# pulseoxintegr.net
KiCad netlist of a schematic drawn in EAGLE
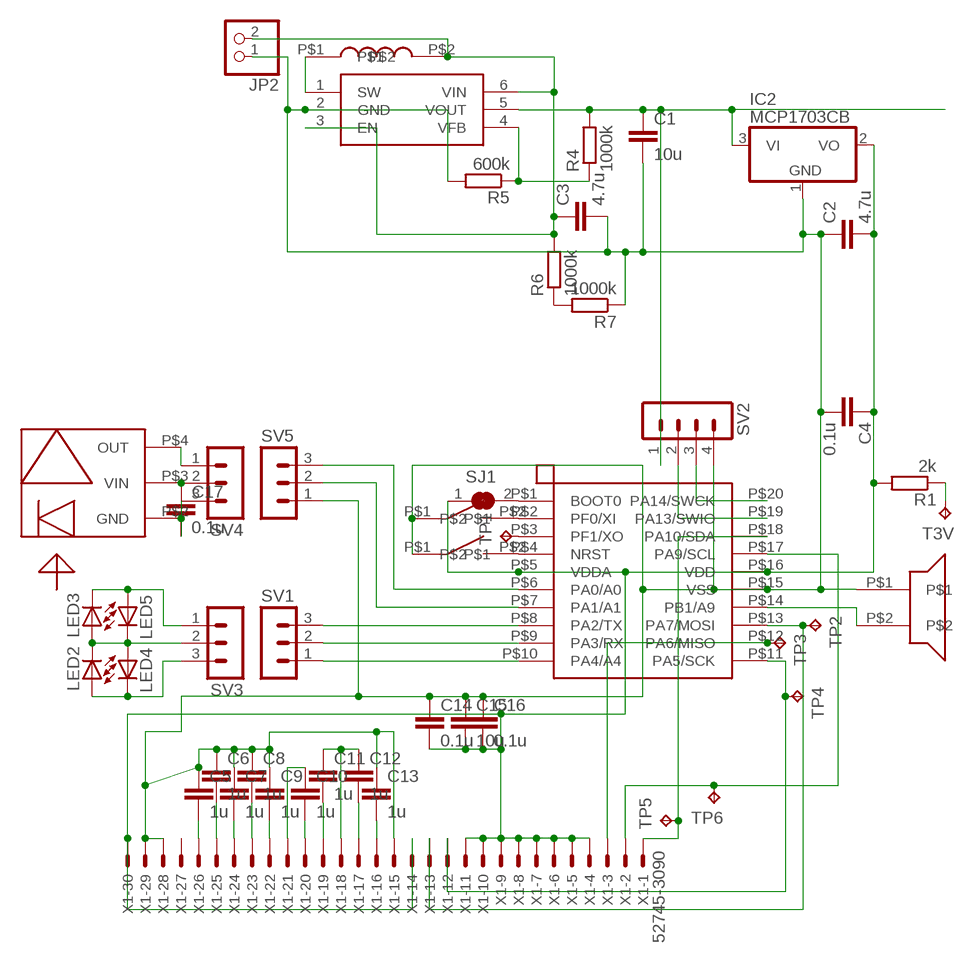
[diagram p0: schematic, sheet 1]

(export (version "E")
  (design (tool "Eeschema 10.0.6"))
  (components
    (comp (ref "C1")
      (value "10u")
      (footprint "eagle-import:C0603K")
      (libsource (lib "eagle-import") (part "C-EUC0603K"))
    )
    (comp (ref "C2")
      (value "4.7u")
      (footprint "eagle-import:C0603K")
      (libsource (lib "eagle-import") (part "C-EUC0603K"))
    )
    (comp (ref "C3")
      (value "4.7u")
      (footprint "eagle-import:C0603K")
      (libsource (lib "eagle-import") (part "C-EUC0603K"))
    )
    (comp (ref "C4")
      (value "0.1u")
      (footprint "eagle-import:C0603K")
      (libsource (lib "eagle-import") (part "C-EUC0603K"))
    )
    (comp (ref "C5")
      (value "1u")
      (footprint "eagle-import:C0603K")
      (libsource (lib "eagle-import") (part "C-EUC0603K"))
    )
    (comp (ref "C6")
      (value "1u")
      (footprint "eagle-import:C0603K")
      (libsource (lib "eagle-import") (part "C-EUC0603K"))
    )
    (comp (ref "C7")
      (value "1u")
      (footprint "eagle-import:C0603K")
      (libsource (lib "eagle-import") (part "C-EUC0603K"))
    )
    (comp (ref "C8")
      (value "1u")
      (footprint "eagle-import:C0603K")
      (libsource (lib "eagle-import") (part "C-EUC0603K"))
    )
    (comp (ref "C9")
      (value "1u")
      (footprint "eagle-import:C0603K")
      (libsource (lib "eagle-import") (part "C-EUC0603K"))
    )
    (comp (ref "C10")
      (value "1u")
      (footprint "eagle-import:C0603K")
      (libsource (lib "eagle-import") (part "C-EUC0603K"))
    )
    (comp (ref "C11")
      (value "1u")
      (footprint "eagle-import:C0603K")
      (libsource (lib "eagle-import") (part "C-EUC0603K"))
    )
    (comp (ref "C12")
      (value "1u")
      (footprint "eagle-import:C0603K")
      (libsource (lib "eagle-import") (part "C-EUC0603K"))
    )
    (comp (ref "C13")
      (value "1u")
      (footprint "eagle-import:C0603K")
      (libsource (lib "eagle-import") (part "C-EUC0603K"))
    )
    (comp (ref "C14")
      (value "0.1u")
      (footprint "eagle-import:C0603K")
      (libsource (lib "eagle-import") (part "C-EUC0603K"))
    )
    (comp (ref "C15")
      (value "10u")
      (footprint "eagle-import:C0603K")
      (libsource (lib "eagle-import") (part "C-EUC0603K"))
    )
    (comp (ref "C16")
      (value "0.1u")
      (footprint "eagle-import:C0603K")
      (libsource (lib "eagle-import") (part "C-EUC0603K"))
    )
    (comp (ref "C17")
      (value "0.1u")
      (footprint "eagle-import:C0603K")
      (libsource (lib "eagle-import") (part "C-EUC0603K"))
    )
    (comp (ref "IC2")
      (value "MCP1703CB")
      (footprint "eagle-import:SOT23")
      (libsource (lib "eagle-import") (part "MCP1703CB"))
    )
    (comp (ref "JP2")
      (value "PINHD-1X2")
      (footprint "eagle-import:1X02")
      (libsource (lib "eagle-import") (part "PINHD-1X2"))
    )
    (comp (ref "LED2")
      (value "LEDCHIP-LED0603")
      (footprint "eagle-import:CHIP-LED0603")
      (libsource (lib "eagle-import") (part "LEDCHIP-LED0603"))
    )
    (comp (ref "LED3")
      (value "LEDCHIP-LED0603")
      (footprint "eagle-import:CHIP-LED0603")
      (libsource (lib "eagle-import") (part "LEDCHIP-LED0603"))
    )
    (comp (ref "LED4")
      (value "LEDCHIP-LED0603")
      (footprint "eagle-import:CHIP-LED0603")
      (libsource (lib "eagle-import") (part "LEDCHIP-LED0603"))
    )
    (comp (ref "LED5")
      (value "LEDCHIP-LED0603")
      (footprint "eagle-import:CHIP-LED0603")
      (libsource (lib "eagle-import") (part "LEDCHIP-LED0603"))
    )
    (comp (ref "R1")
      (value "2k")
      (footprint "eagle-import:R0603")
      (libsource (lib "eagle-import") (part "R-EU_R0603"))
    )
    (comp (ref "R4")
      (value "1000k")
      (footprint "eagle-import:R0603")
      (libsource (lib "eagle-import") (part "R-EU_R0603"))
    )
    (comp (ref "R5")
      (value "600k")
      (footprint "eagle-import:R0603")
      (libsource (lib "eagle-import") (part "R-EU_R0603"))
    )
    (comp (ref "R6")
      (value "1000k")
      (footprint "eagle-import:R0603")
      (libsource (lib "eagle-import") (part "R-EU_R0603"))
    )
    (comp (ref "R7")
      (value "1000k")
      (footprint "eagle-import:R0603")
      (libsource (lib "eagle-import") (part "R-EU_R0603"))
    )
    (comp (ref "SJ1") (value "SJ") (footprint "eagle-import:SJ") (libsource (lib "eagle-import") (part "SJ")))
    (comp (ref "SV1")
      (value "MA03-1")
      (footprint "eagle-import:MA03-1")
      (libsource (lib "eagle-import") (part "MA03-1"))
    )
    (comp (ref "SV2")
      (value "MA04-1")
      (footprint "eagle-import:MA04-1")
      (libsource (lib "eagle-import") (part "MA04-1"))
    )
    (comp (ref "SV3")
      (value "MA03-1")
      (footprint "eagle-import:MA03-1")
      (libsource (lib "eagle-import") (part "MA03-1"))
    )
    (comp (ref "SV4")
      (value "MA03-1")
      (footprint "eagle-import:MA03-1")
      (libsource (lib "eagle-import") (part "MA03-1"))
    )
    (comp (ref "SV5")
      (value "MA03-1")
      (footprint "eagle-import:MA03-1")
      (libsource (lib "eagle-import") (part "MA03-1"))
    )
    (comp (ref "T3V")
      (value "TPTP11R")
      (footprint "eagle-import:TP11R")
      (libsource (lib "eagle-import") (part "TPTP11R"))
    )
    (comp (ref "TP1")
      (value "TPTP11R")
      (footprint "eagle-import:TP11R")
      (libsource (lib "eagle-import") (part "TPTP11R"))
    )
    (comp (ref "TP2")
      (value "TPTP11R")
      (footprint "eagle-import:TP11R")
      (libsource (lib "eagle-import") (part "TPTP11R"))
    )
    (comp (ref "TP3")
      (value "TPTP11R")
      (footprint "eagle-import:TP11R")
      (libsource (lib "eagle-import") (part "TPTP11R"))
    )
    (comp (ref "TP4")
      (value "TPTP11R")
      (footprint "eagle-import:TP11R")
      (libsource (lib "eagle-import") (part "TPTP11R"))
    )
    (comp (ref "TP5")
      (value "TPTP11R")
      (footprint "eagle-import:TP11R")
      (libsource (lib "eagle-import") (part "TPTP11R"))
    )
    (comp (ref "TP6")
      (value "TPTP11R")
      (footprint "eagle-import:TP11R")
      (libsource (lib "eagle-import") (part "TPTP11R"))
    )
    (comp (ref "U$1")
      (value "TSL12T")
      (footprint "eagle-import:TSL12T")
      (libsource (lib "eagle-import") (part "TSL12T"))
    )
    (comp (ref "U$2")
      (value "MCP1640SOT23-6")
      (footprint "eagle-import:SOT23-6L")
      (libsource (lib "eagle-import") (part "MCP1640SOT23-6"))
    )
    (comp (ref "U$3")
      (value "WE-TPC")
      (footprint "eagle-import:WE-TPC")
      (libsource (lib "eagle-import") (part "WE-TPC"))
    )
    (comp (ref "U$4")
      (value "STM32F030F4P6")
      (footprint "eagle-import:TSSOP-20")
      (libsource (lib "eagle-import") (part "STM32F030F4P6"))
    )
    (comp (ref "U$5")
      (value "FSMSM")
      (footprint "eagle-import:FSMSM")
      (libsource (lib "eagle-import") (part "FSMSM"))
    )
    (comp (ref "U$6")
      (value "FSMSM")
      (footprint "eagle-import:FSMSM")
      (libsource (lib "eagle-import") (part "FSMSM"))
    )
    (comp (ref "U$7")
      (value "AT-2440-TWT-R")
      (footprint "eagle-import:AT-2440-TWT-R")
      (libsource (lib "eagle-import") (part "AT-2440-TWT-R"))
    )
    (comp (ref "X1")
      (value "52745-3090")
      (footprint "eagle-import:52745-3090")
      (libsource (lib "eagle-import") (part "52745-3090"))
    )
  )
  (nets
    (net (code "1") (name "Net-(IC2-GND)") (class "Default")
      (node (ref "C1") (pin "2") (pinfunction "2_2") (pintype "passive"))
      (node (ref "C13") (pin "1") (pinfunction "1_1") (pintype "passive"))
      (node (ref "C14") (pin "1") (pinfunction "1_1") (pintype "passive"))
      (node (ref "C15") (pin "1") (pinfunction "1_1") (pintype "passive"))
      (node (ref "C16") (pin "1") (pinfunction "1_1") (pintype "passive"))
      (node (ref "C2") (pin "1") (pinfunction "1_1") (pintype "passive"))
      (node (ref "C3") (pin "2") (pinfunction "2_2") (pintype "passive"))
      (node (ref "C4") (pin "2") (pinfunction "2_2") (pintype "passive"))
      (node (ref "C5") (pin "1") (pinfunction "1_1") (pintype "passive"))
      (node (ref "C6") (pin "1") (pinfunction "1_1") (pintype "passive"))
      (node (ref "C7") (pin "1") (pinfunction "1_1") (pintype "passive"))
      (node (ref "C8") (pin "1") (pinfunction "1_1") (pintype "passive"))
      (node (ref "C9") (pin "1") (pinfunction "1_1") (pintype "passive"))
      (node (ref "IC2") (pin "1") (pinfunction "GND_1") (pintype "passive"))
      (node (ref "JP2") (pin "1") (pinfunction "1_1") (pintype "passive"))
      (node (ref "R5") (pin "2") (pinfunction "2_2") (pintype "passive"))
      (node (ref "R7") (pin "1") (pinfunction "1_1") (pintype "passive"))
      (node (ref "SV2") (pin "4") (pinfunction "4_4") (pintype "passive"))
      (node (ref "SV5") (pin "1") (pinfunction "1_1") (pintype "passive"))
      (node (ref "U$2") (pin "2") (pinfunction "GND_2") (pintype "bidirectional"))
      (node (ref "U$4") (pin "P$15") (pinfunction "VSS_P$15") (pintype "bidirectional"))
      (node (ref "U$5") (pin "P$1") (pinfunction "P$1_P$1") (pintype "bidirectional"))
      (node (ref "U$6") (pin "P$1") (pinfunction "P$1_P$1") (pintype "bidirectional"))
      (node (ref "U$7") (pin "P$1") (pinfunction "P$1_P$1") (pintype "bidirectional"))
      (node (ref "X1") (pin "15") (pinfunction "S_15") (pintype "passive"))
      (node (ref "X1") (pin "28") (pinfunction "S_28") (pintype "passive"))
      (node (ref "X1") (pin "29") (pinfunction "S_29") (pintype "passive"))
    )
    (net (code "2") (name "Net-(IC2-VI)") (class "Default")
      (node (ref "C1") (pin "1") (pinfunction "1_1") (pintype "passive"))
      (node (ref "IC2") (pin "3") (pinfunction "VI_3") (pintype "input"))
      (node (ref "R4") (pin "2") (pinfunction "2_2") (pintype "passive"))
      (node (ref "SV2") (pin "1") (pinfunction "1_1") (pintype "passive"))
      (node (ref "U$2") (pin "5") (pinfunction "VOUT_5") (pintype "bidirectional"))
    )
    (net (code "3") (name "Net-(IC2-VO)") (class "Default")
      (node (ref "C14") (pin "2") (pinfunction "2_2") (pintype "passive"))
      (node (ref "C15") (pin "2") (pinfunction "2_2") (pintype "passive"))
      (node (ref "C16") (pin "2") (pinfunction "2_2") (pintype "passive"))
      (node (ref "C2") (pin "2") (pinfunction "2_2") (pintype "passive"))
      (node (ref "C4") (pin "1") (pinfunction "1_1") (pintype "passive"))
      (node (ref "IC2") (pin "2") (pinfunction "VO_2") (pintype "passive"))
      (node (ref "R1") (pin "2") (pinfunction "2_2") (pintype "passive"))
      (node (ref "SJ1") (pin "1") (pinfunction "1_1") (pintype "passive"))
      (node (ref "U$4") (pin "P$16") (pinfunction "VDD_P$16") (pintype "bidirectional"))
      (node (ref "U$4") (pin "P$5") (pinfunction "VDDA_P$5") (pintype "bidirectional"))
      (node (ref "X1") (pin "10") (pinfunction "S_10") (pintype "passive"))
      (node (ref "X1") (pin "11") (pinfunction "S_11") (pintype "passive"))
      (node (ref "X1") (pin "14") (pinfunction "S_14") (pintype "passive"))
      (node (ref "X1") (pin "30") (pinfunction "S_30") (pintype "passive"))
      (node (ref "X1") (pin "4") (pinfunction "S_4") (pintype "passive"))
      (node (ref "X1") (pin "5") (pinfunction "S_5") (pintype "passive"))
      (node (ref "X1") (pin "6") (pinfunction "S_6") (pintype "passive"))
      (node (ref "X1") (pin "7") (pinfunction "S_7") (pintype "passive"))
      (node (ref "X1") (pin "8") (pinfunction "S_8") (pintype "passive"))
      (node (ref "X1") (pin "9") (pinfunction "S_9") (pintype "passive"))
    )
    (net (code "4") (name "Net-(LED2-PadA)") (class "Default")
      (node (ref "LED2") (pin "A") (pinfunction "A_A") (pintype "passive"))
      (node (ref "LED4") (pin "C") (pinfunction "C_C") (pintype "passive"))
      (node (ref "SV3") (pin "3") (pinfunction "3_3") (pintype "passive"))
    )
    (net (code "5") (name "Net-(LED2-PadC)") (class "Default")
      (node (ref "LED2") (pin "C") (pinfunction "C_C") (pintype "passive"))
      (node (ref "LED3") (pin "A") (pinfunction "A_A") (pintype "passive"))
      (node (ref "LED4") (pin "A") (pinfunction "A_A") (pintype "passive"))
      (node (ref "LED5") (pin "C") (pinfunction "C_C") (pintype "passive"))
      (node (ref "SV3") (pin "2") (pinfunction "2_2") (pintype "passive"))
    )
    (net (code "6") (name "Net-(LED3-PadC)") (class "Default")
      (node (ref "LED3") (pin "C") (pinfunction "C_C") (pintype "passive"))
      (node (ref "LED5") (pin "A") (pinfunction "A_A") (pintype "passive"))
      (node (ref "SV3") (pin "1") (pinfunction "1_1") (pintype "passive"))
    )
    (net (code "7") (name "Net-(R1-Pad1)") (class "Default")
      (node (ref "R1") (pin "1") (pinfunction "1_1") (pintype "passive"))
      (node (ref "T3V") (pin "TP") (pinfunction "TP_TP") (pintype "input"))
    )
    (net (code "8") (name "Net-(R6-Pad1)") (class "Default")
      (node (ref "R6") (pin "1") (pinfunction "1_1") (pintype "passive"))
      (node (ref "R7") (pin "2") (pinfunction "2_2") (pintype "passive"))
    )
    (net (code "9") (name "Net-(U$1-GND)") (class "Default")
      (node (ref "C17") (pin "2") (pinfunction "2_2") (pintype "passive"))
      (node (ref "SV4") (pin "3") (pinfunction "3_3") (pintype "passive"))
      (node (ref "U$1") (pin "P$2") (pinfunction "GND_P$2") (pintype "bidirectional"))
    )
    (net (code "10") (name "Net-(U$1-OUT)") (class "Default")
      (node (ref "SV4") (pin "1") (pinfunction "1_1") (pintype "passive"))
      (node (ref "U$1") (pin "P$4") (pinfunction "OUT_P$4") (pintype "bidirectional"))
    )
    (net (code "11") (name "Net-(U$1-VIN)") (class "Default")
      (node (ref "C17") (pin "1") (pinfunction "1_1") (pintype "passive"))
      (node (ref "SV4") (pin "2") (pinfunction "2_2") (pintype "passive"))
      (node (ref "U$1") (pin "P$3") (pinfunction "VIN_P$3") (pintype "bidirectional"))
    )
    (net (code "12") (name "Net-(U$2-EN)") (class "Default")
      (node (ref "C3") (pin "1") (pinfunction "1_1") (pintype "passive"))
      (node (ref "JP2") (pin "2") (pinfunction "2_2") (pintype "passive"))
      (node (ref "R6") (pin "2") (pinfunction "2_2") (pintype "passive"))
      (node (ref "U$2") (pin "3") (pinfunction "EN_3") (pintype "bidirectional"))
      (node (ref "U$2") (pin "6") (pinfunction "VIN_6") (pintype "bidirectional"))
      (node (ref "U$3") (pin "P$2") (pinfunction "P$2_P$2") (pintype "bidirectional"))
    )
    (net (code "13") (name "Net-(U$2-SW)") (class "Default")
      (node (ref "U$2") (pin "1") (pinfunction "SW_1") (pintype "bidirectional"))
      (node (ref "U$3") (pin "P$1") (pinfunction "P$1_P$1") (pintype "bidirectional"))
    )
    (net (code "14") (name "Net-(U$2-VFB)") (class "Default")
      (node (ref "R4") (pin "1") (pinfunction "1_1") (pintype "passive"))
      (node (ref "R5") (pin "1") (pinfunction "1_1") (pintype "passive"))
      (node (ref "U$2") (pin "4") (pinfunction "VFB_4") (pintype "bidirectional"))
    )
    (net (code "15") (name "Net-(U$4-BOOT0)") (class "Default")
      (node (ref "SJ1") (pin "2") (pinfunction "2_2") (pintype "passive"))
      (node (ref "U$4") (pin "P$1") (pinfunction "BOOT0_P$1") (pintype "bidirectional"))
    )
    (net (code "16") (name "Net-(U$4-NRST)") (class "Default")
      (node (ref "U$4") (pin "P$4") (pinfunction "NRST_P$4") (pintype "bidirectional"))
      (node (ref "U$5") (pin "P$2") (pinfunction "P$2_P$2") (pintype "bidirectional"))
    )
    (net (code "17") (name "Net-(U$4-PA0{slash}A0)") (class "Default")
      (node (ref "SV5") (pin "3") (pinfunction "3_3") (pintype "passive"))
      (node (ref "U$4") (pin "P$6") (pinfunction "PA0/A0_P$6") (pintype "bidirectional"))
    )
    (net (code "18") (name "Net-(U$4-PA1{slash}A1)") (class "Default")
      (node (ref "SV5") (pin "2") (pinfunction "2_2") (pintype "passive"))
      (node (ref "U$4") (pin "P$7") (pinfunction "PA1/A1_P$7") (pintype "bidirectional"))
    )
    (net (code "19") (name "Net-(U$4-PA2{slash}TX)") (class "Default")
      (node (ref "SV1") (pin "3") (pinfunction "3_3") (pintype "passive"))
      (node (ref "U$4") (pin "P$8") (pinfunction "PA2/TX_P$8") (pintype "bidirectional"))
    )
    (net (code "20") (name "Net-(U$4-PA3{slash}RX)") (class "Default")
      (node (ref "SV1") (pin "2") (pinfunction "2_2") (pintype "passive"))
      (node (ref "U$4") (pin "P$9") (pinfunction "PA3/RX_P$9") (pintype "bidirectional"))
    )
    (net (code "21") (name "Net-(U$4-PA4{slash}A4)") (class "Default")
      (node (ref "SV1") (pin "1") (pinfunction "1_1") (pintype "passive"))
      (node (ref "U$4") (pin "P$10") (pinfunction "PA4/A4_P$10") (pintype "bidirectional"))
    )
    (net (code "22") (name "Net-(U$4-PA5{slash}SCK)") (class "Default")
      (node (ref "TP4") (pin "TP") (pinfunction "TP_TP") (pintype "input"))
      (node (ref "U$4") (pin "P$11") (pinfunction "PA5/SCK_P$11") (pintype "bidirectional"))
      (node (ref "X1") (pin "12") (pinfunction "S_12") (pintype "passive"))
    )
    (net (code "23") (name "Net-(U$4-PA6{slash}MISO)") (class "Default")
      (node (ref "TP3") (pin "TP") (pinfunction "TP_TP") (pintype "input"))
      (node (ref "U$4") (pin "P$12") (pinfunction "PA6/MISO_P$12") (pintype "bidirectional"))
      (node (ref "X1") (pin "3") (pinfunction "S_3") (pintype "passive"))
    )
    (net (code "24") (name "Net-(U$4-PA7{slash}MOSI)") (class "Default")
      (node (ref "TP2") (pin "TP") (pinfunction "TP_TP") (pintype "input"))
      (node (ref "U$4") (pin "P$13") (pinfunction "PA7/MOSI_P$13") (pintype "bidirectional"))
      (node (ref "X1") (pin "13") (pinfunction "S_13") (pintype "passive"))
    )
    (net (code "25") (name "Net-(U$4-PA9{slash}SCL)") (class "Default")
      (node (ref "TP6") (pin "TP") (pinfunction "TP_TP") (pintype "input"))
      (node (ref "U$4") (pin "P$17") (pinfunction "PA9/SCL_P$17") (pintype "bidirectional"))
      (node (ref "X1") (pin "2") (pinfunction "S_2") (pintype "passive"))
    )
    (net (code "26") (name "Net-(U$4-PA10{slash}SDA)") (class "Default")
      (node (ref "TP5") (pin "TP") (pinfunction "TP_TP") (pintype "input"))
      (node (ref "U$4") (pin "P$18") (pinfunction "PA10/SDA_P$18") (pintype "bidirectional"))
      (node (ref "X1") (pin "1") (pinfunction "S_1") (pintype "passive"))
    )
    (net (code "27") (name "Net-(U$4-PA13{slash}SWIO)") (class "Default")
      (node (ref "SV2") (pin "2") (pinfunction "2_2") (pintype "passive"))
      (node (ref "U$4") (pin "P$19") (pinfunction "PA13/SWIO_P$19") (pintype "bidirectional"))
    )
    (net (code "28") (name "Net-(U$4-PA14{slash}SWCK)") (class "Default")
      (node (ref "SV2") (pin "3") (pinfunction "3_3") (pintype "passive"))
      (node (ref "U$4") (pin "P$20") (pinfunction "PA14/SWCK_P$20") (pintype "bidirectional"))
    )
    (net (code "29") (name "Net-(U$4-PB1{slash}A9)") (class "Default")
      (node (ref "U$4") (pin "P$14") (pinfunction "PB1/A9_P$14") (pintype "bidirectional"))
      (node (ref "U$7") (pin "P$2") (pinfunction "P$2_P$2") (pintype "bidirectional"))
    )
    (net (code "30") (name "Net-(U$4-PF0{slash}XI)") (class "Default")
      (node (ref "U$4") (pin "P$2") (pinfunction "PF0/XI_P$2") (pintype "bidirectional"))
      (node (ref "U$6") (pin "P$2") (pinfunction "P$2_P$2") (pintype "bidirectional"))
    )
    (net (code "31") (name "Net-(U$4-PF1{slash}XO)") (class "Default")
      (node (ref "TP1") (pin "TP") (pinfunction "TP_TP") (pintype "input"))
      (node (ref "U$4") (pin "P$3") (pinfunction "PF1/XO_P$3") (pintype "bidirectional"))
    )
    (net (code "32") (name "Net-(X1H-S)") (class "Default")
      (node (ref "C13") (pin "2") (pinfunction "2_2") (pintype "passive"))
      (node (ref "X1") (pin "16") (pinfunction "S_16") (pintype "passive"))
    )
    (net (code "33") (name "Net-(X1I-S)") (class "Default")
      (node (ref "C12") (pin "2") (pinfunction "2_2") (pintype "passive"))
      (node (ref "X1") (pin "17") (pinfunction "S_17") (pintype "passive"))
    )
    (net (code "34") (name "Net-(X1J-S)") (class "Default")
      (node (ref "C11") (pin "1") (pinfunction "1_1") (pintype "passive"))
      (node (ref "C12") (pin "1") (pinfunction "1_1") (pintype "passive"))
      (node (ref "X1") (pin "18") (pinfunction "S_18") (pintype "passive"))
    )
    (net (code "35") (name "Net-(X1K-S)") (class "Default")
      (node (ref "C11") (pin "2") (pinfunction "2_2") (pintype "passive"))
      (node (ref "X1") (pin "19") (pinfunction "S_19") (pintype "passive"))
    )
    (net (code "36") (name "Net-(X1M-S)") (class "Default")
      (node (ref "C10") (pin "2") (pinfunction "2_2") (pintype "passive"))
      (node (ref "X1") (pin "20") (pinfunction "S_20") (pintype "passive"))
    )
    (net (code "37") (name "Net-(X1N-S)") (class "Default")
      (node (ref "C10") (pin "1") (pinfunction "1_1") (pintype "passive"))
      (node (ref "X1") (pin "21") (pinfunction "S_21") (pintype "passive"))
    )
    (net (code "38") (name "Net-(X1O-S)") (class "Default")
      (node (ref "C9") (pin "2") (pinfunction "2_2") (pintype "passive"))
      (node (ref "X1") (pin "22") (pinfunction "S_22") (pintype "passive"))
    )
    (net (code "39") (name "Net-(X1P-S)") (class "Default")
      (node (ref "C8") (pin "2") (pinfunction "2_2") (pintype "passive"))
      (node (ref "X1") (pin "23") (pinfunction "S_23") (pintype "passive"))
    )
    (net (code "40") (name "Net-(X1Q-S)") (class "Default")
      (node (ref "C7") (pin "2") (pinfunction "2_2") (pintype "passive"))
      (node (ref "X1") (pin "24") (pinfunction "S_24") (pintype "passive"))
    )
    (net (code "41") (name "Net-(X1R-S)") (class "Default")
      (node (ref "C6") (pin "2") (pinfunction "2_2") (pintype "passive"))
      (node (ref "X1") (pin "25") (pinfunction "S_25") (pintype "passive"))
    )
    (net (code "42") (name "Net-(X1S-S)") (class "Default")
      (node (ref "C5") (pin "2") (pinfunction "2_2") (pintype "passive"))
      (node (ref "X1") (pin "26") (pinfunction "S_26") (pintype "passive"))
    )
    (net (code "43") (name "unconnected-(X1T-S-Pad27)") (class "Default")
      (node (ref "X1") (pin "27") (pinfunction "S_27") (pintype "passive"))
    )
  )
)
